# DSPA.net
KiCad netlist of a schematic drawn in Altium Designer
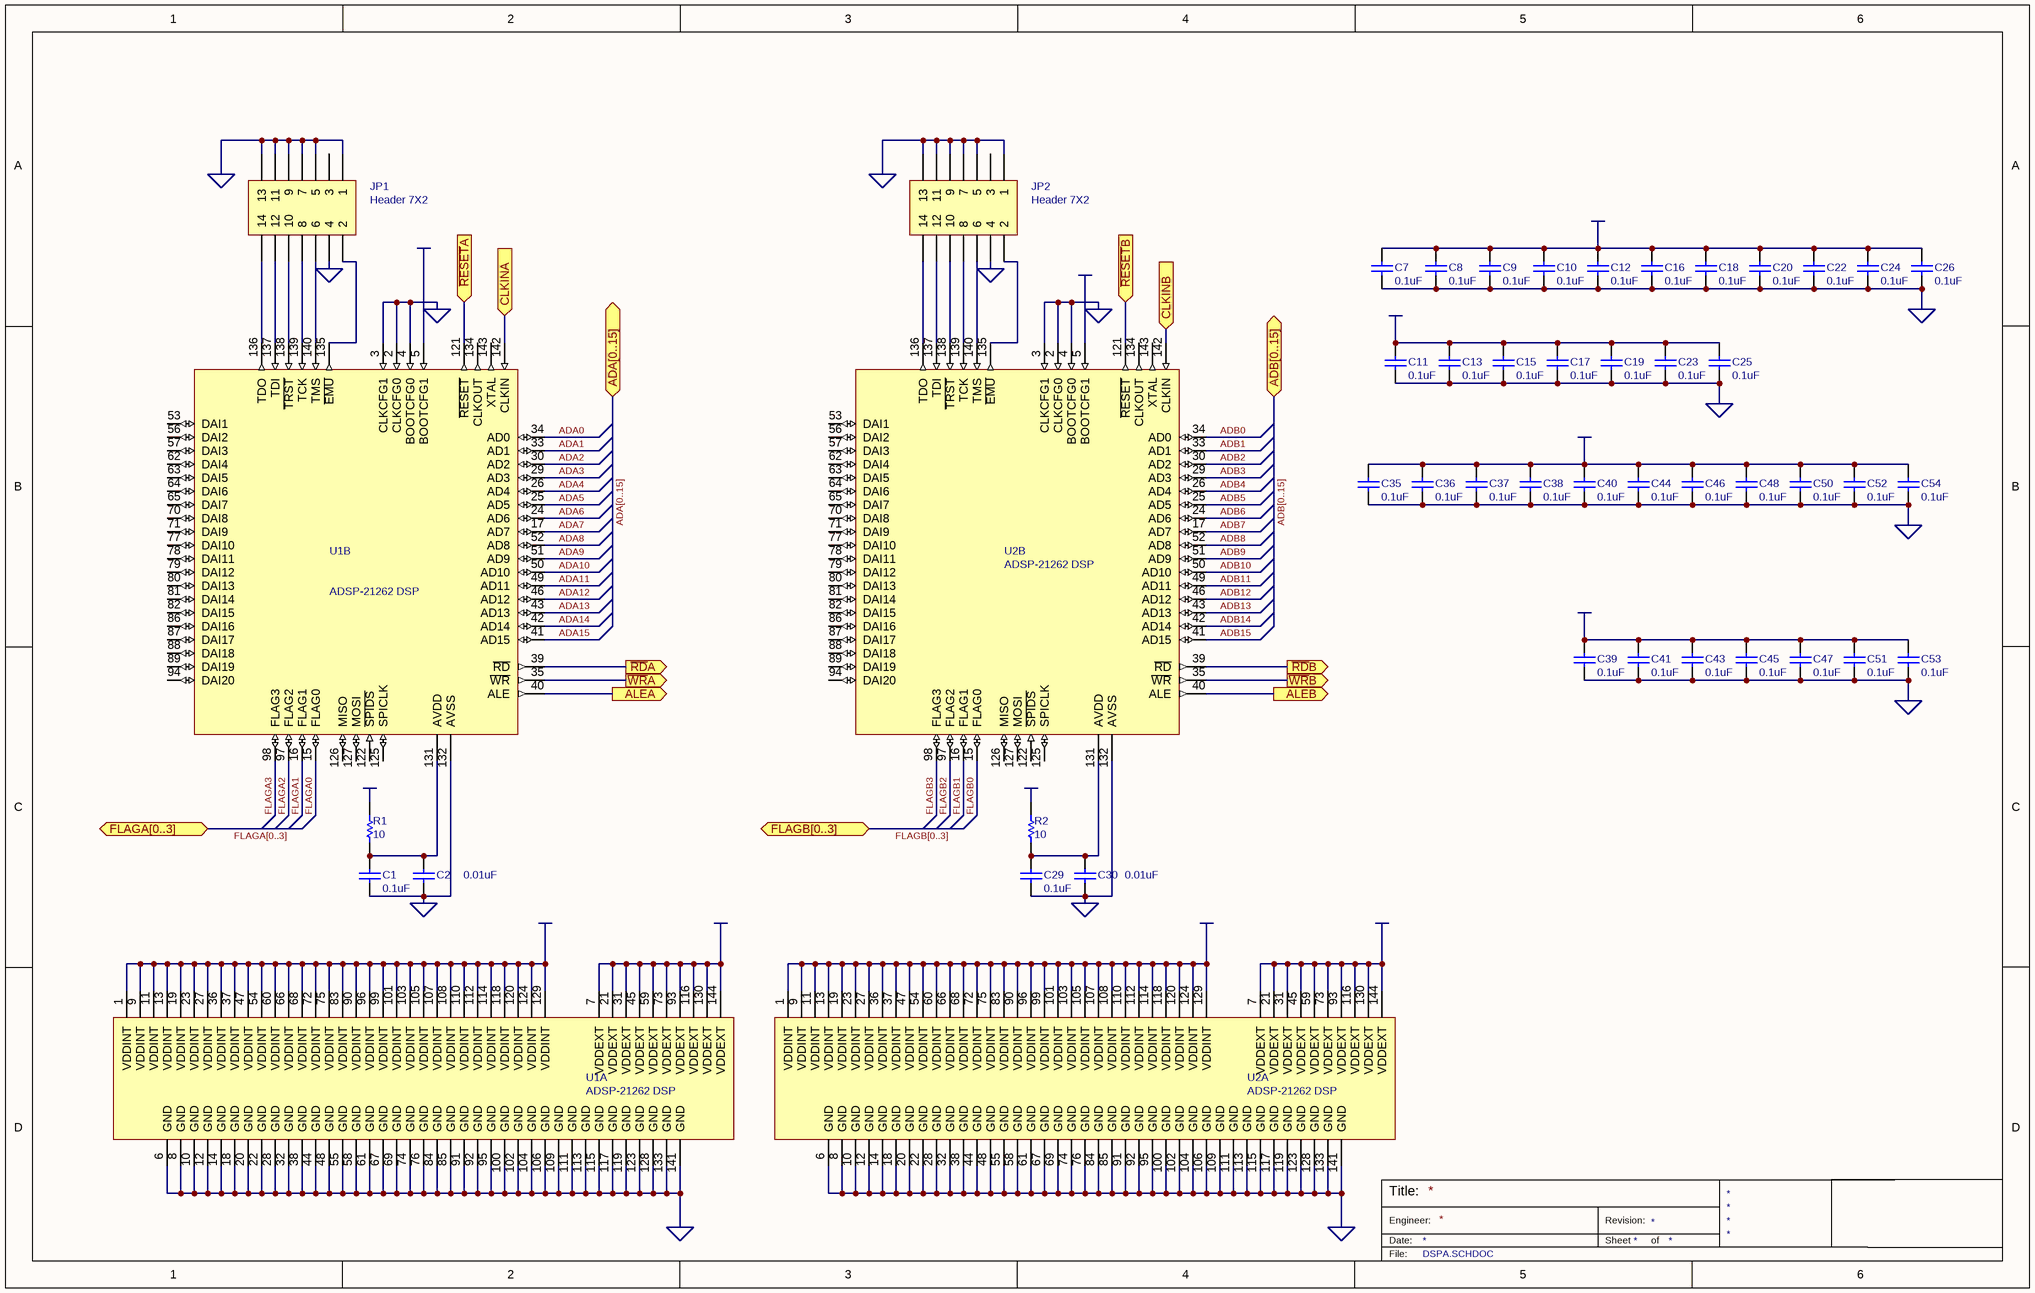
[diagram p0: DSPA.SCHDOC]

(export (version "E")
  (design (tool "Eeschema 10.0.6"))
  (components
    (comp (ref "C1")
      (value "0.1uF")
      (footprint "CC1005-0402")
      (description "Capacitor")
      (fields
        (field (name "MANUFACTURER") "Generic Components")
        (field (name "Comment") "Cap")
        (field (name "PUBLISHER") "Altium Limited")
      )
      (libsource (lib "Miscellaneous Devices") (part "Cap"))
    )
    (comp (ref "C2")
      (value "0.01uF")
      (footprint "CC1005-0402")
      (description "Capacitor")
      (fields
        (field (name "MANUFACTURER") "Generic Components")
        (field (name "Comment") "Cap")
        (field (name "PUBLISHER") "Altium Limited")
      )
      (libsource (lib "Miscellaneous Devices") (part "Cap"))
    )
    (comp (ref "C7")
      (value "0.1uF")
      (footprint "CC1005-0402")
      (description "Capacitor")
      (fields
        (field (name "MANUFACTURER") "Generic Components")
        (field (name "Comment") "Cap")
        (field (name "PUBLISHER") "Altium Limited")
      )
      (libsource (lib "Miscellaneous Devices") (part "Cap"))
    )
    (comp (ref "C8")
      (value "0.1uF")
      (footprint "CC1005-0402")
      (description "Capacitor")
      (fields
        (field (name "MANUFACTURER") "Generic Components")
        (field (name "Comment") "Cap")
        (field (name "PUBLISHER") "Altium Limited")
      )
      (libsource (lib "Miscellaneous Devices") (part "Cap"))
    )
    (comp (ref "C9")
      (value "0.1uF")
      (footprint "CC1005-0402")
      (description "Capacitor")
      (fields
        (field (name "MANUFACTURER") "Generic Components")
        (field (name "Comment") "Cap")
        (field (name "PUBLISHER") "Altium Limited")
      )
      (libsource (lib "Miscellaneous Devices") (part "Cap"))
    )
    (comp (ref "C10")
      (value "0.1uF")
      (footprint "CC1005-0402")
      (description "Capacitor")
      (fields
        (field (name "MANUFACTURER") "Generic Components")
        (field (name "Comment") "Cap")
        (field (name "PUBLISHER") "Altium Limited")
      )
      (libsource (lib "Miscellaneous Devices") (part "Cap"))
    )
    (comp (ref "C11")
      (value "0.1uF")
      (footprint "CC1005-0402")
      (description "Capacitor")
      (fields
        (field (name "MANUFACTURER") "Generic Components")
        (field (name "Comment") "Cap")
        (field (name "PUBLISHER") "Altium Limited")
      )
      (libsource (lib "Miscellaneous Devices") (part "Cap"))
    )
    (comp (ref "C12")
      (value "0.1uF")
      (footprint "CC1005-0402")
      (description "Capacitor")
      (fields
        (field (name "MANUFACTURER") "Generic Components")
        (field (name "Comment") "Cap")
        (field (name "PUBLISHER") "Altium Limited")
      )
      (libsource (lib "Miscellaneous Devices") (part "Cap"))
    )
    (comp (ref "C13")
      (value "0.1uF")
      (footprint "CC1005-0402")
      (description "Capacitor")
      (fields
        (field (name "MANUFACTURER") "Generic Components")
        (field (name "Comment") "Cap")
        (field (name "PUBLISHER") "Altium Limited")
      )
      (libsource (lib "Miscellaneous Devices") (part "Cap"))
    )
    (comp (ref "C15")
      (value "0.1uF")
      (footprint "CC1005-0402")
      (description "Capacitor")
      (fields
        (field (name "MANUFACTURER") "Generic Components")
        (field (name "Comment") "Cap")
        (field (name "PUBLISHER") "Altium Limited")
      )
      (libsource (lib "Miscellaneous Devices") (part "Cap"))
    )
    (comp (ref "C16")
      (value "0.1uF")
      (footprint "CC1005-0402")
      (description "Capacitor")
      (fields
        (field (name "MANUFACTURER") "Generic Components")
        (field (name "Comment") "Cap")
        (field (name "PUBLISHER") "Altium Limited")
      )
      (libsource (lib "Miscellaneous Devices") (part "Cap"))
    )
    (comp (ref "C17")
      (value "0.1uF")
      (footprint "CC1005-0402")
      (description "Capacitor")
      (fields
        (field (name "MANUFACTURER") "Generic Components")
        (field (name "Comment") "Cap")
        (field (name "PUBLISHER") "Altium Limited")
      )
      (libsource (lib "Miscellaneous Devices") (part "Cap"))
    )
    (comp (ref "C18")
      (value "0.1uF")
      (footprint "CC1005-0402")
      (description "Capacitor")
      (fields
        (field (name "MANUFACTURER") "Generic Components")
        (field (name "Comment") "Cap")
        (field (name "PUBLISHER") "Altium Limited")
      )
      (libsource (lib "Miscellaneous Devices") (part "Cap"))
    )
    (comp (ref "C19")
      (value "0.1uF")
      (footprint "CC1005-0402")
      (description "Capacitor")
      (fields
        (field (name "MANUFACTURER") "Generic Components")
        (field (name "Comment") "Cap")
        (field (name "PUBLISHER") "Altium Limited")
      )
      (libsource (lib "Miscellaneous Devices") (part "Cap"))
    )
    (comp (ref "C20")
      (value "0.1uF")
      (footprint "CC1005-0402")
      (description "Capacitor")
      (fields
        (field (name "MANUFACTURER") "Generic Components")
        (field (name "Comment") "Cap")
        (field (name "PUBLISHER") "Altium Limited")
      )
      (libsource (lib "Miscellaneous Devices") (part "Cap"))
    )
    (comp (ref "C22")
      (value "0.1uF")
      (footprint "CC1005-0402")
      (description "Capacitor")
      (fields
        (field (name "MANUFACTURER") "Generic Components")
        (field (name "Comment") "Cap")
        (field (name "PUBLISHER") "Altium Limited")
      )
      (libsource (lib "Miscellaneous Devices") (part "Cap"))
    )
    (comp (ref "C23")
      (value "0.1uF")
      (footprint "CC1005-0402")
      (description "Capacitor")
      (fields
        (field (name "MANUFACTURER") "Generic Components")
        (field (name "Comment") "Cap")
        (field (name "PUBLISHER") "Altium Limited")
      )
      (libsource (lib "Miscellaneous Devices") (part "Cap"))
    )
    (comp (ref "C24")
      (value "0.1uF")
      (footprint "CC1005-0402")
      (description "Capacitor")
      (fields
        (field (name "MANUFACTURER") "Generic Components")
        (field (name "Comment") "Cap")
        (field (name "PUBLISHER") "Altium Limited")
      )
      (libsource (lib "Miscellaneous Devices") (part "Cap"))
    )
    (comp (ref "C25")
      (value "0.1uF")
      (footprint "CC1005-0402")
      (description "Capacitor")
      (fields
        (field (name "MANUFACTURER") "Generic Components")
        (field (name "Comment") "Cap")
        (field (name "PUBLISHER") "Altium Limited")
      )
      (libsource (lib "Miscellaneous Devices") (part "Cap"))
    )
    (comp (ref "C26")
      (value "0.1uF")
      (footprint "CC1005-0402")
      (description "Capacitor")
      (fields
        (field (name "MANUFACTURER") "Generic Components")
        (field (name "Comment") "Cap")
        (field (name "PUBLISHER") "Altium Limited")
      )
      (libsource (lib "Miscellaneous Devices") (part "Cap"))
    )
    (comp (ref "C29")
      (value "0.1uF")
      (footprint "CC1005-0402")
      (description "Capacitor")
      (fields
        (field (name "MANUFACTURER") "Generic Components")
        (field (name "Comment") "Cap")
        (field (name "PUBLISHER") "Altium Limited")
      )
      (libsource (lib "Miscellaneous Devices") (part "Cap"))
    )
    (comp (ref "C30")
      (value "0.01uF")
      (footprint "CC1005-0402")
      (description "Capacitor")
      (fields
        (field (name "MANUFACTURER") "Generic Components")
        (field (name "Comment") "Cap")
        (field (name "PUBLISHER") "Altium Limited")
      )
      (libsource (lib "Miscellaneous Devices") (part "Cap"))
    )
    (comp (ref "C35")
      (value "0.1uF")
      (footprint "CC1005-0402")
      (description "Capacitor")
      (fields
        (field (name "MANUFACTURER") "Generic Components")
        (field (name "Comment") "Cap")
        (field (name "PUBLISHER") "Altium Limited")
      )
      (libsource (lib "Miscellaneous Devices") (part "Cap"))
    )
    (comp (ref "C36")
      (value "0.1uF")
      (footprint "CC1005-0402")
      (description "Capacitor")
      (fields
        (field (name "MANUFACTURER") "Generic Components")
        (field (name "Comment") "Cap")
        (field (name "PUBLISHER") "Altium Limited")
      )
      (libsource (lib "Miscellaneous Devices") (part "Cap"))
    )
    (comp (ref "C37")
      (value "0.1uF")
      (footprint "CC1005-0402")
      (description "Capacitor")
      (fields
        (field (name "MANUFACTURER") "Generic Components")
        (field (name "Comment") "Cap")
        (field (name "PUBLISHER") "Altium Limited")
      )
      (libsource (lib "Miscellaneous Devices") (part "Cap"))
    )
    (comp (ref "C38")
      (value "0.1uF")
      (footprint "CC1005-0402")
      (description "Capacitor")
      (fields
        (field (name "MANUFACTURER") "Generic Components")
        (field (name "Comment") "Cap")
        (field (name "PUBLISHER") "Altium Limited")
      )
      (libsource (lib "Miscellaneous Devices") (part "Cap"))
    )
    (comp (ref "C39")
      (value "0.1uF")
      (footprint "CC1005-0402")
      (description "Capacitor")
      (fields
        (field (name "MANUFACTURER") "Generic Components")
        (field (name "Comment") "Cap")
        (field (name "PUBLISHER") "Altium Limited")
      )
      (libsource (lib "Miscellaneous Devices") (part "Cap"))
    )
    (comp (ref "C40")
      (value "0.1uF")
      (footprint "CC1005-0402")
      (description "Capacitor")
      (fields
        (field (name "MANUFACTURER") "Generic Components")
        (field (name "Comment") "Cap")
        (field (name "PUBLISHER") "Altium Limited")
      )
      (libsource (lib "Miscellaneous Devices") (part "Cap"))
    )
    (comp (ref "C41")
      (value "0.1uF")
      (footprint "CC1005-0402")
      (description "Capacitor")
      (fields
        (field (name "MANUFACTURER") "Generic Components")
        (field (name "Comment") "Cap")
        (field (name "PUBLISHER") "Altium Limited")
      )
      (libsource (lib "Miscellaneous Devices") (part "Cap"))
    )
    (comp (ref "C43")
      (value "0.1uF")
      (footprint "CC1005-0402")
      (description "Capacitor")
      (fields
        (field (name "MANUFACTURER") "Generic Components")
        (field (name "Comment") "Cap")
        (field (name "PUBLISHER") "Altium Limited")
      )
      (libsource (lib "Miscellaneous Devices") (part "Cap"))
    )
    (comp (ref "C44")
      (value "0.1uF")
      (footprint "CC1005-0402")
      (description "Capacitor")
      (fields
        (field (name "MANUFACTURER") "Generic Components")
        (field (name "Comment") "Cap")
        (field (name "PUBLISHER") "Altium Limited")
      )
      (libsource (lib "Miscellaneous Devices") (part "Cap"))
    )
    (comp (ref "C45")
      (value "0.1uF")
      (footprint "CC1005-0402")
      (description "Capacitor")
      (fields
        (field (name "MANUFACTURER") "Generic Components")
        (field (name "Comment") "Cap")
        (field (name "PUBLISHER") "Altium Limited")
      )
      (libsource (lib "Miscellaneous Devices") (part "Cap"))
    )
    (comp (ref "C46")
      (value "0.1uF")
      (footprint "CC1005-0402")
      (description "Capacitor")
      (fields
        (field (name "MANUFACTURER") "Generic Components")
        (field (name "Comment") "Cap")
        (field (name "PUBLISHER") "Altium Limited")
      )
      (libsource (lib "Miscellaneous Devices") (part "Cap"))
    )
    (comp (ref "C47")
      (value "0.1uF")
      (footprint "CC1005-0402")
      (description "Capacitor")
      (fields
        (field (name "MANUFACTURER") "Generic Components")
        (field (name "Comment") "Cap")
        (field (name "PUBLISHER") "Altium Limited")
      )
      (libsource (lib "Miscellaneous Devices") (part "Cap"))
    )
    (comp (ref "C48")
      (value "0.1uF")
      (footprint "CC1005-0402")
      (description "Capacitor")
      (fields
        (field (name "MANUFACTURER") "Generic Components")
        (field (name "Comment") "Cap")
        (field (name "PUBLISHER") "Altium Limited")
      )
      (libsource (lib "Miscellaneous Devices") (part "Cap"))
    )
    (comp (ref "C50")
      (value "0.1uF")
      (footprint "CC1005-0402")
      (description "Capacitor")
      (fields
        (field (name "MANUFACTURER") "Generic Components")
        (field (name "Comment") "Cap")
        (field (name "PUBLISHER") "Altium Limited")
      )
      (libsource (lib "Miscellaneous Devices") (part "Cap"))
    )
    (comp (ref "C51")
      (value "0.1uF")
      (footprint "CC1005-0402")
      (description "Capacitor")
      (fields
        (field (name "MANUFACTURER") "Generic Components")
        (field (name "Comment") "Cap")
        (field (name "PUBLISHER") "Altium Limited")
      )
      (libsource (lib "Miscellaneous Devices") (part "Cap"))
    )
    (comp (ref "C52")
      (value "0.1uF")
      (footprint "CC1005-0402")
      (description "Capacitor")
      (fields
        (field (name "MANUFACTURER") "Generic Components")
        (field (name "Comment") "Cap")
        (field (name "PUBLISHER") "Altium Limited")
      )
      (libsource (lib "Miscellaneous Devices") (part "Cap"))
    )
    (comp (ref "C53")
      (value "0.1uF")
      (footprint "CC1005-0402")
      (description "Capacitor")
      (fields
        (field (name "MANUFACTURER") "Generic Components")
        (field (name "Comment") "Cap")
        (field (name "PUBLISHER") "Altium Limited")
      )
      (libsource (lib "Miscellaneous Devices") (part "Cap"))
    )
    (comp (ref "C54")
      (value "0.1uF")
      (footprint "CC1005-0402")
      (description "Capacitor")
      (fields
        (field (name "MANUFACTURER") "Generic Components")
        (field (name "Comment") "Cap")
        (field (name "PUBLISHER") "Altium Limited")
      )
      (libsource (lib "Miscellaneous Devices") (part "Cap"))
    )
    (comp (ref "JP1")
      (value "Header 7X2")
      (footprint "HDR2X7")
      (description "Header, 7-Pin, Dual row")
      (fields (field (name "MANUFACTURER") "Generic Components") (field (name "PUBLISHER") "Altium Limited"))
      (libsource (lib "Miscellaneous Connectors") (part "Header 7X2"))
    )
    (comp (ref "JP2")
      (value "Header 7X2")
      (footprint "HDR2X7")
      (description "Header, 7-Pin, Dual row")
      (fields (field (name "MANUFACTURER") "Generic Components") (field (name "PUBLISHER") "Altium Limited"))
      (libsource (lib "Miscellaneous Connectors") (part "Header 7X2"))
    )
    (comp (ref "R1")
      (value "10")
      (footprint "CR1608-0603")
      (description "Resistor")
      (fields
        (field (name "MANUFACTURER") "Generic Components")
        (field (name "Comment") "Res1")
        (field (name "PUBLISHER") "Altium Limited")
      )
      (libsource (lib "Miscellaneous Devices") (part "Res1"))
    )
    (comp (ref "R2")
      (value "10")
      (footprint "CR1608-0603")
      (description "Resistor")
      (fields
        (field (name "MANUFACTURER") "Generic Components")
        (field (name "Comment") "Res1")
        (field (name "PUBLISHER") "Altium Limited")
      )
      (libsource (lib "Miscellaneous Devices") (part "Res1"))
    )
    (comp (ref "U1")
      (value "ADSP-21262 DSP")
      (footprint "F-QFP20X20-G144/N")
      (description "SHARC 200 MHz 32-bit floating-point SIMD DSP")
      (libsource (lib "parts") (part "ADSP-21262"))
    )
    (comp (ref "U2")
      (value "ADSP-21262 DSP")
      (footprint "F-QFP20X20-G144/N")
      (description "SHARC 200 MHz 32-bit floating-point SIMD DSP")
      (libsource (lib "parts") (part "ADSP-21262"))
    )
  )
  (nets
    (net (code "1") (name "+1.2VCC") (class "Default")
      (node (ref "C10") (pin "2") (pinfunction "2_2") (pintype "passive"))
      (node (ref "C12") (pin "2") (pinfunction "2_2") (pintype "passive"))
      (node (ref "C16") (pin "2") (pinfunction "2_2") (pintype "passive"))
      (node (ref "C18") (pin "2") (pinfunction "2_2") (pintype "passive"))
      (node (ref "C20") (pin "2") (pinfunction "2_2") (pintype "passive"))
      (node (ref "C22") (pin "2") (pinfunction "2_2") (pintype "passive"))
      (node (ref "C24") (pin "2") (pinfunction "2_2") (pintype "passive"))
      (node (ref "C26") (pin "2") (pinfunction "2_2") (pintype "passive"))
      (node (ref "C35") (pin "2") (pinfunction "2_2") (pintype "passive"))
      (node (ref "C36") (pin "2") (pinfunction "2_2") (pintype "passive"))
      (node (ref "C37") (pin "2") (pinfunction "2_2") (pintype "passive"))
      (node (ref "C38") (pin "2") (pinfunction "2_2") (pintype "passive"))
      (node (ref "C40") (pin "2") (pinfunction "2_2") (pintype "passive"))
      (node (ref "C44") (pin "2") (pinfunction "2_2") (pintype "passive"))
      (node (ref "C46") (pin "2") (pinfunction "2_2") (pintype "passive"))
      (node (ref "C48") (pin "2") (pinfunction "2_2") (pintype "passive"))
      (node (ref "C50") (pin "2") (pinfunction "2_2") (pintype "passive"))
      (node (ref "C52") (pin "2") (pinfunction "2_2") (pintype "passive"))
      (node (ref "C54") (pin "2") (pinfunction "2_2") (pintype "passive"))
      (node (ref "C7") (pin "2") (pinfunction "2_2") (pintype "passive"))
      (node (ref "C8") (pin "2") (pinfunction "2_2") (pintype "passive"))
      (node (ref "C9") (pin "2") (pinfunction "2_2") (pintype "passive"))
      (node (ref "R1") (pin "1") (pinfunction "1_1") (pintype "passive"))
      (node (ref "R2") (pin "1") (pinfunction "1_1") (pintype "passive"))
      (node (ref "U1") (pin "1") (pinfunction "VDDINT_1") (pintype "power_in"))
      (node (ref "U1") (pin "101") (pinfunction "VDDINT_101") (pintype "power_in"))
      (node (ref "U1") (pin "103") (pinfunction "VDDINT_103") (pintype "power_in"))
      (node (ref "U1") (pin "105") (pinfunction "VDDINT_105") (pintype "power_in"))
      (node (ref "U1") (pin "107") (pinfunction "VDDINT_107") (pintype "power_in"))
      (node (ref "U1") (pin "108") (pinfunction "VDDINT_108") (pintype "power_in"))
      (node (ref "U1") (pin "11") (pinfunction "VDDINT_11") (pintype "power_in"))
      (node (ref "U1") (pin "110") (pinfunction "VDDINT_110") (pintype "power_in"))
      (node (ref "U1") (pin "112") (pinfunction "VDDINT_112") (pintype "power_in"))
      (node (ref "U1") (pin "114") (pinfunction "VDDINT_114") (pintype "power_in"))
      (node (ref "U1") (pin "118") (pinfunction "VDDINT_118") (pintype "power_in"))
      (node (ref "U1") (pin "120") (pinfunction "VDDINT_120") (pintype "power_in"))
      (node (ref "U1") (pin "124") (pinfunction "VDDINT_124") (pintype "power_in"))
      (node (ref "U1") (pin "129") (pinfunction "VDDINT_129") (pintype "power_in"))
      (node (ref "U1") (pin "13") (pinfunction "VDDINT_13") (pintype "power_in"))
      (node (ref "U1") (pin "19") (pinfunction "VDDINT_19") (pintype "power_in"))
      (node (ref "U1") (pin "23") (pinfunction "VDDINT_23") (pintype "power_in"))
      (node (ref "U1") (pin "27") (pinfunction "VDDINT_27") (pintype "power_in"))
      (node (ref "U1") (pin "36") (pinfunction "VDDINT_36") (pintype "power_in"))
      (node (ref "U1") (pin "37") (pinfunction "VDDINT_37") (pintype "power_in"))
      (node (ref "U1") (pin "47") (pinfunction "VDDINT_47") (pintype "power_in"))
      (node (ref "U1") (pin "54") (pinfunction "VDDINT_54") (pintype "power_in"))
      (node (ref "U1") (pin "60") (pinfunction "VDDINT_60") (pintype "power_in"))
      (node (ref "U1") (pin "66") (pinfunction "VDDINT_66") (pintype "power_in"))
      (node (ref "U1") (pin "68") (pinfunction "VDDINT_68") (pintype "power_in"))
      (node (ref "U1") (pin "72") (pinfunction "VDDINT_72") (pintype "power_in"))
      (node (ref "U1") (pin "75") (pinfunction "VDDINT_75") (pintype "power_in"))
      (node (ref "U1") (pin "83") (pinfunction "VDDINT_83") (pintype "power_in"))
      (node (ref "U1") (pin "9") (pinfunction "VDDINT_9") (pintype "power_in"))
      (node (ref "U1") (pin "90") (pinfunction "VDDINT_90") (pintype "power_in"))
      (node (ref "U1") (pin "96") (pinfunction "VDDINT_96") (pintype "power_in"))
      (node (ref "U1") (pin "99") (pinfunction "VDDINT_99") (pintype "power_in"))
      (node (ref "U2") (pin "1") (pinfunction "VDDINT_1") (pintype "power_in"))
      (node (ref "U2") (pin "101") (pinfunction "VDDINT_101") (pintype "power_in"))
      (node (ref "U2") (pin "103") (pinfunction "VDDINT_103") (pintype "power_in"))
      (node (ref "U2") (pin "105") (pinfunction "VDDINT_105") (pintype "power_in"))
      (node (ref "U2") (pin "107") (pinfunction "VDDINT_107") (pintype "power_in"))
      (node (ref "U2") (pin "108") (pinfunction "VDDINT_108") (pintype "power_in"))
      (node (ref "U2") (pin "11") (pinfunction "VDDINT_11") (pintype "power_in"))
      (node (ref "U2") (pin "110") (pinfunction "VDDINT_110") (pintype "power_in"))
      (node (ref "U2") (pin "112") (pinfunction "VDDINT_112") (pintype "power_in"))
      (node (ref "U2") (pin "114") (pinfunction "VDDINT_114") (pintype "power_in"))
      (node (ref "U2") (pin "118") (pinfunction "VDDINT_118") (pintype "power_in"))
      (node (ref "U2") (pin "120") (pinfunction "VDDINT_120") (pintype "power_in"))
      (node (ref "U2") (pin "124") (pinfunction "VDDINT_124") (pintype "power_in"))
      (node (ref "U2") (pin "129") (pinfunction "VDDINT_129") (pintype "power_in"))
      (node (ref "U2") (pin "13") (pinfunction "VDDINT_13") (pintype "power_in"))
      (node (ref "U2") (pin "19") (pinfunction "VDDINT_19") (pintype "power_in"))
      (node (ref "U2") (pin "23") (pinfunction "VDDINT_23") (pintype "power_in"))
      (node (ref "U2") (pin "27") (pinfunction "VDDINT_27") (pintype "power_in"))
      (node (ref "U2") (pin "36") (pinfunction "VDDINT_36") (pintype "power_in"))
      (node (ref "U2") (pin "37") (pinfunction "VDDINT_37") (pintype "power_in"))
      (node (ref "U2") (pin "47") (pinfunction "VDDINT_47") (pintype "power_in"))
      (node (ref "U2") (pin "54") (pinfunction "VDDINT_54") (pintype "power_in"))
      (node (ref "U2") (pin "60") (pinfunction "VDDINT_60") (pintype "power_in"))
      (node (ref "U2") (pin "66") (pinfunction "VDDINT_66") (pintype "power_in"))
      (node (ref "U2") (pin "68") (pinfunction "VDDINT_68") (pintype "power_in"))
      (node (ref "U2") (pin "72") (pinfunction "VDDINT_72") (pintype "power_in"))
      (node (ref "U2") (pin "75") (pinfunction "VDDINT_75") (pintype "power_in"))
      (node (ref "U2") (pin "83") (pinfunction "VDDINT_83") (pintype "power_in"))
      (node (ref "U2") (pin "9") (pinfunction "VDDINT_9") (pintype "power_in"))
      (node (ref "U2") (pin "90") (pinfunction "VDDINT_90") (pintype "power_in"))
      (node (ref "U2") (pin "96") (pinfunction "VDDINT_96") (pintype "power_in"))
      (node (ref "U2") (pin "99") (pinfunction "VDDINT_99") (pintype "power_in"))
    )
    (net (code "2") (name "/ADA0") (class "Default")
      (node (ref "U1") (pin "34") (pinfunction "AD0_34") (pintype "bidirectional"))
    )
    (net (code "3") (name "/ADA1") (class "Default")
      (node (ref "U1") (pin "33") (pinfunction "AD1_33") (pintype "bidirectional"))
    )
    (net (code "4") (name "/ADA2") (class "Default")
      (node (ref "U1") (pin "30") (pinfunction "AD2_30") (pintype "bidirectional"))
    )
    (net (code "5") (name "/ADA3") (class "Default")
      (node (ref "U1") (pin "29") (pinfunction "AD3_29") (pintype "bidirectional"))
    )
    (net (code "6") (name "/ADA4") (class "Default")
      (node (ref "U1") (pin "26") (pinfunction "AD4_26") (pintype "bidirectional"))
    )
    (net (code "7") (name "/ADA5") (class "Default")
      (node (ref "U1") (pin "25") (pinfunction "AD5_25") (pintype "bidirectional"))
    )
    (net (code "8") (name "/ADA6") (class "Default")
      (node (ref "U1") (pin "24") (pinfunction "AD6_24") (pintype "bidirectional"))
    )
    (net (code "9") (name "/ADA7") (class "Default")
      (node (ref "U1") (pin "17") (pinfunction "AD7_17") (pintype "bidirectional"))
    )
    (net (code "10") (name "/ADA8") (class "Default")
      (node (ref "U1") (pin "52") (pinfunction "AD8_52") (pintype "bidirectional"))
    )
    (net (code "11") (name "/ADA9") (class "Default")
      (node (ref "U1") (pin "51") (pinfunction "AD9_51") (pintype "bidirectional"))
    )
    (net (code "12") (name "/ADA10") (class "Default")
      (node (ref "U1") (pin "50") (pinfunction "AD10_50") (pintype "bidirectional"))
    )
    (net (code "13") (name "/ADA11") (class "Default")
      (node (ref "U1") (pin "49") (pinfunction "AD11_49") (pintype "bidirectional"))
    )
    (net (code "14") (name "/ADA12") (class "Default")
      (node (ref "U1") (pin "46") (pinfunction "AD12_46") (pintype "bidirectional"))
    )
    (net (code "15") (name "/ADA13") (class "Default")
      (node (ref "U1") (pin "43") (pinfunction "AD13_43") (pintype "bidirectional"))
    )
    (net (code "16") (name "/ADA14") (class "Default")
      (node (ref "U1") (pin "42") (pinfunction "AD14_42") (pintype "bidirectional"))
    )
    (net (code "17") (name "/ADA15") (class "Default")
      (node (ref "U1") (pin "41") (pinfunction "AD15_41") (pintype "bidirectional"))
    )
    (net (code "19") (name "/ADB0") (class "Default")
      (node (ref "U2") (pin "34") (pinfunction "AD0_34") (pintype "bidirectional"))
    )
    (net (code "20") (name "/ADB1") (class "Default")
      (node (ref "U2") (pin "33") (pinfunction "AD1_33") (pintype "bidirectional"))
    )
    (net (code "21") (name "/ADB2") (class "Default")
      (node (ref "U2") (pin "30") (pinfunction "AD2_30") (pintype "bidirectional"))
    )
    (net (code "22") (name "/ADB3") (class "Default")
      (node (ref "U2") (pin "29") (pinfunction "AD3_29") (pintype "bidirectional"))
    )
    (net (code "23") (name "/ADB4") (class "Default")
      (node (ref "U2") (pin "26") (pinfunction "AD4_26") (pintype "bidirectional"))
    )
    (net (code "24") (name "/ADB5") (class "Default")
      (node (ref "U2") (pin "25") (pinfunction "AD5_25") (pintype "bidirectional"))
    )
    (net (code "25") (name "/ADB6") (class "Default")
      (node (ref "U2") (pin "24") (pinfunction "AD6_24") (pintype "bidirectional"))
    )
    (net (code "26") (name "/ADB7") (class "Default")
      (node (ref "U2") (pin "17") (pinfunction "AD7_17") (pintype "bidirectional"))
    )
    (net (code "27") (name "/ADB8") (class "Default")
      (node (ref "U2") (pin "52") (pinfunction "AD8_52") (pintype "bidirectional"))
    )
    (net (code "28") (name "/ADB9") (class "Default")
      (node (ref "U2") (pin "51") (pinfunction "AD9_51") (pintype "bidirectional"))
    )
    (net (code "29") (name "/ADB10") (class "Default")
      (node (ref "U2") (pin "50") (pinfunction "AD10_50") (pintype "bidirectional"))
    )
    (net (code "30") (name "/ADB11") (class "Default")
      (node (ref "U2") (pin "49") (pinfunction "AD11_49") (pintype "bidirectional"))
    )
    (net (code "31") (name "/ADB12") (class "Default")
      (node (ref "U2") (pin "46") (pinfunction "AD12_46") (pintype "bidirectional"))
    )
    (net (code "32") (name "/ADB13") (class "Default")
      (node (ref "U2") (pin "43") (pinfunction "AD13_43") (pintype "bidirectional"))
    )
    (net (code "33") (name "/ADB14") (class "Default")
      (node (ref "U2") (pin "42") (pinfunction "AD14_42") (pintype "bidirectional"))
    )
    (net (code "34") (name "/ADB15") (class "Default")
      (node (ref "U2") (pin "41") (pinfunction "AD15_41") (pintype "bidirectional"))
    )
    (net (code "36") (name "/ALEA") (class "Default")
      (node (ref "U1") (pin "40") (pinfunction "ALE_40") (pintype "output"))
    )
    (net (code "37") (name "/ALEB") (class "Default")
      (node (ref "U2") (pin "40") (pinfunction "ALE_40") (pintype "output"))
    )
    (net (code "38") (name "/CLKINA") (class "Default")
      (node (ref "U1") (pin "142") (pinfunction "CLKIN_142") (pintype "input"))
    )
    (net (code "39") (name "/CLKINB") (class "Default")
      (node (ref "U2") (pin "142") (pinfunction "CLKIN_142") (pintype "input"))
    )
    (net (code "40") (name "/FLAGA0") (class "Default")
      (node (ref "U1") (pin "15") (pinfunction "FLAG0_15") (pintype "bidirectional"))
    )
    (net (code "41") (name "/FLAGA1") (class "Default")
      (node (ref "U1") (pin "16") (pinfunction "FLAG1_16") (pintype "bidirectional"))
    )
    (net (code "42") (name "/FLAGA2") (class "Default")
      (node (ref "U1") (pin "97") (pinfunction "FLAG2_97") (pintype "bidirectional"))
    )
    (net (code "43") (name "/FLAGA3") (class "Default")
      (node (ref "U1") (pin "98") (pinfunction "FLAG3_98") (pintype "bidirectional"))
    )
    (net (code "45") (name "/FLAGB0") (class "Default")
      (node (ref "U2") (pin "15") (pinfunction "FLAG0_15") (pintype "bidirectional"))
    )
    (net (code "46") (name "/FLAGB1") (class "Default")
      (node (ref "U2") (pin "16") (pinfunction "FLAG1_16") (pintype "bidirectional"))
    )
    (net (code "47") (name "/FLAGB2") (class "Default")
      (node (ref "U2") (pin "97") (pinfunction "FLAG2_97") (pintype "bidirectional"))
    )
    (net (code "48") (name "/FLAGB3") (class "Default")
      (node (ref "U2") (pin "98") (pinfunction "FLAG3_98") (pintype "bidirectional"))
    )
    (net (code "50") (name "/~{RD}A") (class "Default")
      (node (ref "U1") (pin "39") (pinfunction "~{RD}_39") (pintype "output"))
    )
    (net (code "51") (name "/~{RD}B") (class "Default")
      (node (ref "U2") (pin "39") (pinfunction "~{RD}_39") (pintype "output"))
    )
    (net (code "52") (name "/~{RESET}A") (class "Default")
      (node (ref "U1") (pin "121") (pinfunction "~{RESET}_121") (pintype "output"))
    )
    (net (code "53") (name "/~{RESET}B") (class "Default")
      (node (ref "U2") (pin "121") (pinfunction "~{RESET}_121") (pintype "output"))
    )
    (net (code "54") (name "/~{WR}A") (class "Default")
      (node (ref "U1") (pin "35") (pinfunction "~{WR}_35") (pintype "output"))
    )
    (net (code "55") (name "/~{WR}B") (class "Default")
      (node (ref "U2") (pin "35") (pinfunction "~{WR}_35") (pintype "output"))
    )
    (net (code "56") (name "GND") (class "Default")
      (node (ref "C1") (pin "1") (pinfunction "1_1") (pintype "passive"))
      (node (ref "C10") (pin "1") (pinfunction "1_1") (pintype "passive"))
      (node (ref "C11") (pin "1") (pinfunction "1_1") (pintype "passive"))
      (node (ref "C12") (pin "1") (pinfunction "1_1") (pintype "passive"))
      (node (ref "C13") (pin "1") (pinfunction "1_1") (pintype "passive"))
      (node (ref "C15") (pin "1") (pinfunction "1_1") (pintype "passive"))
      (node (ref "C16") (pin "1") (pinfunction "1_1") (pintype "passive"))
      (node (ref "C17") (pin "1") (pinfunction "1_1") (pintype "passive"))
      (node (ref "C18") (pin "1") (pinfunction "1_1") (pintype "passive"))
      (node (ref "C19") (pin "1") (pinfunction "1_1") (pintype "passive"))
      (node (ref "C2") (pin "1") (pinfunction "1_1") (pintype "passive"))
      (node (ref "C20") (pin "1") (pinfunction "1_1") (pintype "passive"))
      (node (ref "C22") (pin "1") (pinfunction "1_1") (pintype "passive"))
      (node (ref "C23") (pin "1") (pinfunction "1_1") (pintype "passive"))
      (node (ref "C24") (pin "1") (pinfunction "1_1") (pintype "passive"))
      (node (ref "C25") (pin "1") (pinfunction "1_1") (pintype "passive"))
      (node (ref "C26") (pin "1") (pinfunction "1_1") (pintype "passive"))
      (node (ref "C29") (pin "1") (pinfunction "1_1") (pintype "passive"))
      (node (ref "C30") (pin "1") (pinfunction "1_1") (pintype "passive"))
      (node (ref "C35") (pin "1") (pinfunction "1_1") (pintype "passive"))
      (node (ref "C36") (pin "1") (pinfunction "1_1") (pintype "passive"))
      (node (ref "C37") (pin "1") (pinfunction "1_1") (pintype "passive"))
      (node (ref "C38") (pin "1") (pinfunction "1_1") (pintype "passive"))
      (node (ref "C39") (pin "1") (pinfunction "1_1") (pintype "passive"))
      (node (ref "C40") (pin "1") (pinfunction "1_1") (pintype "passive"))
      (node (ref "C41") (pin "1") (pinfunction "1_1") (pintype "passive"))
      (node (ref "C43") (pin "1") (pinfunction "1_1") (pintype "passive"))
      (node (ref "C44") (pin "1") (pinfunction "1_1") (pintype "passive"))
      (node (ref "C45") (pin "1") (pinfunction "1_1") (pintype "passive"))
      (node (ref "C46") (pin "1") (pinfunction "1_1") (pintype "passive"))
      (node (ref "C47") (pin "1") (pinfunction "1_1") (pintype "passive"))
      (node (ref "C48") (pin "1") (pinfunction "1_1") (pintype "passive"))
      (node (ref "C50") (pin "1") (pinfunction "1_1") (pintype "passive"))
      (node (ref "C51") (pin "1") (pinfunction "1_1") (pintype "passive"))
      (node (ref "C52") (pin "1") (pinfunction "1_1") (pintype "passive"))
      (node (ref "C53") (pin "1") (pinfunction "1_1") (pintype "passive"))
      (node (ref "C54") (pin "1") (pinfunction "1_1") (pintype "passive"))
      (node (ref "C7") (pin "1") (pinfunction "1_1") (pintype "passive"))
      (node (ref "C8") (pin "1") (pinfunction "1_1") (pintype "passive"))
      (node (ref "C9") (pin "1") (pinfunction "1_1") (pintype "passive"))
      (node (ref "JP1") (pin "1") (pinfunction "1_1") (pintype "passive"))
      (node (ref "JP1") (pin "11") (pinfunction "11_11") (pintype "passive"))
      (node (ref "JP1") (pin "13") (pinfunction "13_13") (pintype "passive"))
      (node (ref "JP1") (pin "4") (pinfunction "4_4") (pintype "passive"))
      (node (ref "JP1") (pin "5") (pinfunction "5_5") (pintype "passive"))
      (node (ref "JP1") (pin "7") (pinfunction "7_7") (pintype "passive"))
      (node (ref "JP1") (pin "9") (pinfunction "9_9") (pintype "passive"))
      (node (ref "JP2") (pin "1") (pinfunction "1_1") (pintype "passive"))
      (node (ref "JP2") (pin "11") (pinfunction "11_11") (pintype "passive"))
      (node (ref "JP2") (pin "13") (pinfunction "13_13") (pintype "passive"))
      (node (ref "JP2") (pin "4") (pinfunction "4_4") (pintype "passive"))
      (node (ref "JP2") (pin "5") (pinfunction "5_5") (pintype "passive"))
      (node (ref "JP2") (pin "7") (pinfunction "7_7") (pintype "passive"))
      (node (ref "JP2") (pin "9") (pinfunction "9_9") (pintype "passive"))
      (node (ref "U1") (pin "10") (pinfunction "GND_10") (pintype "power_in"))
      (node (ref "U1") (pin "100") (pinfunction "GND_100") (pintype "power_in"))
      (node (ref "U1") (pin "102") (pinfunction "GND_102") (pintype "power_in"))
      (node (ref "U1") (pin "104") (pinfunction "GND_104") (pintype "power_in"))
      (node (ref "U1") (pin "106") (pinfunction "GND_106") (pintype "power_in"))
      (node (ref "U1") (pin "109") (pinfunction "GND_109") (pintype "power_in"))
      (node (ref "U1") (pin "111") (pinfunction "GND_111") (pintype "power_in"))
      (node (ref "U1") (pin "113") (pinfunction "GND_113") (pintype "power_in"))
      (node (ref "U1") (pin "115") (pinfunction "GND_115") (pintype "power_in"))
      (node (ref "U1") (pin "117") (pinfunction "GND_117") (pintype "power_in"))
      (node (ref "U1") (pin "119") (pinfunction "GND_119") (pintype "power_in"))
      (node (ref "U1") (pin "12") (pinfunction "GND_12") (pintype "power_in"))
      (node (ref "U1") (pin "123") (pinfunction "GND_123") (pintype "power_in"))
      (node (ref "U1") (pin "128") (pinfunction "GND_128") (pintype "power_in"))
      (node (ref "U1") (pin "132") (pinfunction "AVSS_132") (pintype "power_in"))
      (node (ref "U1") (pin "133") (pinfunction "GND_133") (pintype "power_in"))
      (node (ref "U1") (pin "14") (pinfunction "GND_14") (pintype "power_in"))
      (node (ref "U1") (pin "141") (pinfunction "GND_141") (pintype "power_in"))
      (node (ref "U1") (pin "18") (pinfunction "GND_18") (pintype "power_in"))
      (node (ref "U1") (pin "2") (pinfunction "CLKCFG0_2") (pintype "input"))
      (node (ref "U1") (pin "20") (pinfunction "GND_20") (pintype "power_in"))
      (node (ref "U1") (pin "22") (pinfunction "GND_22") (pintype "power_in"))
      (node (ref "U1") (pin "28") (pinfunction "GND_28") (pintype "power_in"))
      (node (ref "U1") (pin "3") (pinfunction "CLKCFG1_3") (pintype "input"))
      (node (ref "U1") (pin "32") (pinfunction "GND_32") (pintype "power_in"))
      (node (ref "U1") (pin "38") (pinfunction "GND_38") (pintype "power_in"))
      (node (ref "U1") (pin "4") (pinfunction "BOOTCFG0_4") (pintype "input"))
      (node (ref "U1") (pin "44") (pinfunction "GND_44") (pintype "power_in"))
      (node (ref "U1") (pin "48") (pinfunction "GND_48") (pintype "power_in"))
      (node (ref "U1") (pin "55") (pinfunction "GND_55") (pintype "power_in"))
      (node (ref "U1") (pin "58") (pinfunction "GND_58") (pintype "power_in"))
      (node (ref "U1") (pin "6") (pinfunction "GND_6") (pintype "power_in"))
      (node (ref "U1") (pin "61") (pinfunction "GND_61") (pintype "power_in"))
      (node (ref "U1") (pin "67") (pinfunction "GND_67") (pintype "power_in"))
      (node (ref "U1") (pin "69") (pinfunction "GND_69") (pintype "power_in"))
      (node (ref "U1") (pin "74") (pinfunction "GND_74") (pintype "power_in"))
      (node (ref "U1") (pin "76") (pinfunction "GND_76") (pintype "power_in"))
      (node (ref "U1") (pin "8") (pinfunction "GND_8") (pintype "power_in"))
      (node (ref "U1") (pin "84") (pinfunction "GND_84") (pintype "power_in"))
      (node (ref "U1") (pin "85") (pinfunction "GND_85") (pintype "power_in"))
      (node (ref "U1") (pin "91") (pinfunction "GND_91") (pintype "power_in"))
      (node (ref "U1") (pin "92") (pinfunction "GND_92") (pintype "power_in"))
      (node (ref "U1") (pin "95") (pinfunction "GND_95") (pintype "power_in"))
      (node (ref "U2") (pin "10") (pinfunction "GND_10") (pintype "power_in"))
      (node (ref "U2") (pin "100") (pinfunction "GND_100") (pintype "power_in"))
      (node (ref "U2") (pin "102") (pinfunction "GND_102") (pintype "power_in"))
      (node (ref "U2") (pin "104") (pinfunction "GND_104") (pintype "power_in"))
      (node (ref "U2") (pin "106") (pinfunction "GND_106") (pintype "power_in"))
      (node (ref "U2") (pin "109") (pinfunction "GND_109") (pintype "power_in"))
      (node (ref "U2") (pin "111") (pinfunction "GND_111") (pintype "power_in"))
      (node (ref "U2") (pin "113") (pinfunction "GND_113") (pintype "power_in"))
      (node (ref "U2") (pin "115") (pinfunction "GND_115") (pintype "power_in"))
      (node (ref "U2") (pin "117") (pinfunction "GND_117") (pintype "power_in"))
      (node (ref "U2") (pin "119") (pinfunction "GND_119") (pintype "power_in"))
      (node (ref "U2") (pin "12") (pinfunction "GND_12") (pintype "power_in"))
      (node (ref "U2") (pin "123") (pinfunction "GND_123") (pintype "power_in"))
      (node (ref "U2") (pin "128") (pinfunction "GND_128") (pintype "power_in"))
      (node (ref "U2") (pin "132") (pinfunction "AVSS_132") (pintype "power_in"))
      (node (ref "U2") (pin "133") (pinfunction "GND_133") (pintype "power_in"))
      (node (ref "U2") (pin "14") (pinfunction "GND_14") (pintype "power_in"))
      (node (ref "U2") (pin "141") (pinfunction "GND_141") (pintype "power_in"))
      (node (ref "U2") (pin "18") (pinfunction "GND_18") (pintype "power_in"))
      (node (ref "U2") (pin "2") (pinfunction "CLKCFG0_2") (pintype "input"))
      (node (ref "U2") (pin "20") (pinfunction "GND_20") (pintype "power_in"))
      (node (ref "U2") (pin "22") (pinfunction "GND_22") (pintype "power_in"))
      (node (ref "U2") (pin "28") (pinfunction "GND_28") (pintype "power_in"))
      (node (ref "U2") (pin "3") (pinfunction "CLKCFG1_3") (pintype "input"))
      (node (ref "U2") (pin "32") (pinfunction "GND_32") (pintype "power_in"))
      (node (ref "U2") (pin "38") (pinfunction "GND_38") (pintype "power_in"))
      (node (ref "U2") (pin "4") (pinfunction "BOOTCFG0_4") (pintype "input"))
      (node (ref "U2") (pin "44") (pinfunction "GND_44") (pintype "power_in"))
      (node (ref "U2") (pin "48") (pinfunction "GND_48") (pintype "power_in"))
      (node (ref "U2") (pin "55") (pinfunction "GND_55") (pintype "power_in"))
      (node (ref "U2") (pin "58") (pinfunction "GND_58") (pintype "power_in"))
      (node (ref "U2") (pin "6") (pinfunction "GND_6") (pintype "power_in"))
      (node (ref "U2") (pin "61") (pinfunction "GND_61") (pintype "power_in"))
      (node (ref "U2") (pin "67") (pinfunction "GND_67") (pintype "power_in"))
      (node (ref "U2") (pin "69") (pinfunction "GND_69") (pintype "power_in"))
      (node (ref "U2") (pin "74") (pinfunction "GND_74") (pintype "power_in"))
      (node (ref "U2") (pin "76") (pinfunction "GND_76") (pintype "power_in"))
      (node (ref "U2") (pin "8") (pinfunction "GND_8") (pintype "power_in"))
      (node (ref "U2") (pin "84") (pinfunction "GND_84") (pintype "power_in"))
      (node (ref "U2") (pin "85") (pinfunction "GND_85") (pintype "power_in"))
      (node (ref "U2") (pin "91") (pinfunction "GND_91") (pintype "power_in"))
      (node (ref "U2") (pin "92") (pinfunction "GND_92") (pintype "power_in"))
      (node (ref "U2") (pin "95") (pinfunction "GND_95") (pintype "power_in"))
    )
    (net (code "57") (name "Net-(U1B-AVDD)") (class "Default")
      (node (ref "C1") (pin "2") (pinfunction "2_2") (pintype "passive"))
      (node (ref "C2") (pin "2") (pinfunction "2_2") (pintype "passive"))
      (node (ref "R1") (pin "2") (pinfunction "2_2") (pintype "passive"))
      (node (ref "U1") (pin "131") (pinfunction "AVDD_131") (pintype "power_in"))
    )
    (net (code "58") (name "Net-(U1B-TCK)") (class "Default")
      (node (ref "JP1") (pin "8") (pinfunction "8_8") (pintype "passive"))
      (node (ref "U1") (pin "139") (pinfunction "TCK_139") (pintype "input"))
    )
    (net (code "59") (name "Net-(U1B-TDI)") (class "Default")
      (node (ref "JP1") (pin "12") (pinfunction "12_12") (pintype "passive"))
      (node (ref "U1") (pin "137") (pinfunction "TDI_137") (pintype "input"))
    )
    (net (code "60") (name "Net-(U1B-TDO)") (class "Default")
      (node (ref "JP1") (pin "14") (pinfunction "14_14") (pintype "passive"))
      (node (ref "U1") (pin "136") (pinfunction "TDO_136") (pintype "output"))
    )
    (net (code "61") (name "Net-(U1B-TMS)") (class "Default")
      (node (ref "JP1") (pin "6") (pinfunction "6_6") (pintype "passive"))
      (node (ref "U1") (pin "140") (pinfunction "TMS_140") (pintype "input"))
    )
    (net (code "62") (name "Net-(U1B-~{EMU})") (class "Default")
      (node (ref "JP1") (pin "2") (pinfunction "2_2") (pintype "passive"))
      (node (ref "U1") (pin "135") (pinfunction "~{EMU}_135") (pintype "output"))
    )
    (net (code "63") (name "Net-(U1B-~{TRST})") (class "Default")
      (node (ref "JP1") (pin "10") (pinfunction "10_10") (pintype "passive"))
      (node (ref "U1") (pin "138") (pinfunction "~{TRST}_138") (pintype "input"))
    )
    (net (code "64") (name "Net-(U2B-AVDD)") (class "Default")
      (node (ref "C29") (pin "2") (pinfunction "2_2") (pintype "passive"))
      (node (ref "C30") (pin "2") (pinfunction "2_2") (pintype "passive"))
      (node (ref "R2") (pin "2") (pinfunction "2_2") (pintype "passive"))
      (node (ref "U2") (pin "131") (pinfunction "AVDD_131") (pintype "power_in"))
    )
    (net (code "65") (name "Net-(U2B-TCK)") (class "Default")
      (node (ref "JP2") (pin "8") (pinfunction "8_8") (pintype "passive"))
      (node (ref "U2") (pin "139") (pinfunction "TCK_139") (pintype "input"))
    )
    (net (code "66") (name "Net-(U2B-TDI)") (class "Default")
      (node (ref "JP2") (pin "12") (pinfunction "12_12") (pintype "passive"))
      (node (ref "U2") (pin "137") (pinfunction "TDI_137") (pintype "input"))
    )
    (net (code "67") (name "Net-(U2B-TDO)") (class "Default")
      (node (ref "JP2") (pin "14") (pinfunction "14_14") (pintype "passive"))
      (node (ref "U2") (pin "136") (pinfunction "TDO_136") (pintype "output"))
    )
    (net (code "68") (name "Net-(U2B-TMS)") (class "Default")
      (node (ref "JP2") (pin "6") (pinfunction "6_6") (pintype "passive"))
      (node (ref "U2") (pin "140") (pinfunction "TMS_140") (pintype "input"))
    )
    (net (code "69") (name "Net-(U2B-~{EMU})") (class "Default")
      (node (ref "JP2") (pin "2") (pinfunction "2_2") (pintype "passive"))
      (node (ref "U2") (pin "135") (pinfunction "~{EMU}_135") (pintype "output"))
    )
    (net (code "70") (name "Net-(U2B-~{TRST})") (class "Default")
      (node (ref "JP2") (pin "10") (pinfunction "10_10") (pintype "passive"))
      (node (ref "U2") (pin "138") (pinfunction "~{TRST}_138") (pintype "input"))
    )
    (net (code "71") (name "VCC") (class "Default")
      (node (ref "C11") (pin "2") (pinfunction "2_2") (pintype "passive"))
      (node (ref "C13") (pin "2") (pinfunction "2_2") (pintype "passive"))
      (node (ref "C15") (pin "2") (pinfunction "2_2") (pintype "passive"))
      (node (ref "C17") (pin "2") (pinfunction "2_2") (pintype "passive"))
      (node (ref "C19") (pin "2") (pinfunction "2_2") (pintype "passive"))
      (node (ref "C23") (pin "2") (pinfunction "2_2") (pintype "passive"))
      (node (ref "C25") (pin "2") (pinfunction "2_2") (pintype "passive"))
      (node (ref "C39") (pin "2") (pinfunction "2_2") (pintype "passive"))
      (node (ref "C41") (pin "2") (pinfunction "2_2") (pintype "passive"))
      (node (ref "C43") (pin "2") (pinfunction "2_2") (pintype "passive"))
      (node (ref "C45") (pin "2") (pinfunction "2_2") (pintype "passive"))
      (node (ref "C47") (pin "2") (pinfunction "2_2") (pintype "passive"))
      (node (ref "C51") (pin "2") (pinfunction "2_2") (pintype "passive"))
      (node (ref "C53") (pin "2") (pinfunction "2_2") (pintype "passive"))
      (node (ref "U1") (pin "116") (pinfunction "VDDEXT_116") (pintype "power_in"))
      (node (ref "U1") (pin "130") (pinfunction "VDDEXT_130") (pintype "power_in"))
      (node (ref "U1") (pin "144") (pinfunction "VDDEXT_144") (pintype "power_in"))
      (node (ref "U1") (pin "21") (pinfunction "VDDEXT_21") (pintype "power_in"))
      (node (ref "U1") (pin "31") (pinfunction "VDDEXT_31") (pintype "power_in"))
      (node (ref "U1") (pin "45") (pinfunction "VDDEXT_45") (pintype "power_in"))
      (node (ref "U1") (pin "5") (pinfunction "BOOTCFG1_5") (pintype "input"))
      (node (ref "U1") (pin "59") (pinfunction "VDDEXT_59") (pintype "power_in"))
      (node (ref "U1") (pin "7") (pinfunction "VDDEXT_7") (pintype "power_in"))
      (node (ref "U1") (pin "73") (pinfunction "VDDEXT_73") (pintype "power_in"))
      (node (ref "U1") (pin "93") (pinfunction "VDDEXT_93") (pintype "power_in"))
      (node (ref "U2") (pin "116") (pinfunction "VDDEXT_116") (pintype "power_in"))
      (node (ref "U2") (pin "130") (pinfunction "VDDEXT_130") (pintype "power_in"))
      (node (ref "U2") (pin "144") (pinfunction "VDDEXT_144") (pintype "power_in"))
      (node (ref "U2") (pin "21") (pinfunction "VDDEXT_21") (pintype "power_in"))
      (node (ref "U2") (pin "31") (pinfunction "VDDEXT_31") (pintype "power_in"))
      (node (ref "U2") (pin "45") (pinfunction "VDDEXT_45") (pintype "power_in"))
      (node (ref "U2") (pin "5") (pinfunction "BOOTCFG1_5") (pintype "input"))
      (node (ref "U2") (pin "59") (pinfunction "VDDEXT_59") (pintype "power_in"))
      (node (ref "U2") (pin "7") (pinfunction "VDDEXT_7") (pintype "power_in"))
      (node (ref "U2") (pin "73") (pinfunction "VDDEXT_73") (pintype "power_in"))
      (node (ref "U2") (pin "93") (pinfunction "VDDEXT_93") (pintype "power_in"))
    )
    (net (code "72") (name "unconnected-(JP1-Pad3)") (class "Default")
      (node (ref "JP1") (pin "3") (pinfunction "3_3") (pintype "passive"))
    )
    (net (code "73") (name "unconnected-(JP2-Pad3)") (class "Default")
      (node (ref "JP2") (pin "3") (pinfunction "3_3") (pintype "passive"))
    )
    (net (code "74") (name "unconnected-(U1B-CLKOUT-Pad134)") (class "Default")
      (node (ref "U1") (pin "134") (pinfunction "CLKOUT_134") (pintype "output"))
    )
    (net (code "75") (name "unconnected-(U1B-DAI1-Pad53)") (class "Default")
      (node (ref "U1") (pin "53") (pinfunction "DAI1_53") (pintype "bidirectional"))
    )
    (net (code "76") (name "unconnected-(U1B-DAI2-Pad56)") (class "Default")
      (node (ref "U1") (pin "56") (pinfunction "DAI2_56") (pintype "bidirectional"))
    )
    (net (code "77") (name "unconnected-(U1B-DAI3-Pad57)") (class "Default")
      (node (ref "U1") (pin "57") (pinfunction "DAI3_57") (pintype "bidirectional"))
    )
    (net (code "78") (name "unconnected-(U1B-DAI4-Pad62)") (class "Default")
      (node (ref "U1") (pin "62") (pinfunction "DAI4_62") (pintype "bidirectional"))
    )
    (net (code "79") (name "unconnected-(U1B-DAI5-Pad63)") (class "Default")
      (node (ref "U1") (pin "63") (pinfunction "DAI5_63") (pintype "bidirectional"))
    )
    (net (code "80") (name "unconnected-(U1B-DAI6-Pad64)") (class "Default")
      (node (ref "U1") (pin "64") (pinfunction "DAI6_64") (pintype "bidirectional"))
    )
    (net (code "81") (name "unconnected-(U1B-DAI7-Pad65)") (class "Default")
      (node (ref "U1") (pin "65") (pinfunction "DAI7_65") (pintype "bidirectional"))
    )
    (net (code "82") (name "unconnected-(U1B-DAI8-Pad70)") (class "Default")
      (node (ref "U1") (pin "70") (pinfunction "DAI8_70") (pintype "bidirectional"))
    )
    (net (code "83") (name "unconnected-(U1B-DAI9-Pad71)") (class "Default")
      (node (ref "U1") (pin "71") (pinfunction "DAI9_71") (pintype "bidirectional"))
    )
    (net (code "84") (name "unconnected-(U1B-DAI10-Pad77)") (class "Default")
      (node (ref "U1") (pin "77") (pinfunction "DAI10_77") (pintype "bidirectional"))
    )
    (net (code "85") (name "unconnected-(U1B-DAI11-Pad78)") (class "Default")
      (node (ref "U1") (pin "78") (pinfunction "DAI11_78") (pintype "bidirectional"))
    )
    (net (code "86") (name "unconnected-(U1B-DAI12-Pad79)") (class "Default")
      (node (ref "U1") (pin "79") (pinfunction "DAI12_79") (pintype "bidirectional"))
    )
    (net (code "87") (name "unconnected-(U1B-DAI13-Pad80)") (class "Default")
      (node (ref "U1") (pin "80") (pinfunction "DAI13_80") (pintype "bidirectional"))
    )
    (net (code "88") (name "unconnected-(U1B-DAI14-Pad81)") (class "Default")
      (node (ref "U1") (pin "81") (pinfunction "DAI14_81") (pintype "bidirectional"))
    )
    (net (code "89") (name "unconnected-(U1B-DAI15-Pad82)") (class "Default")
      (node (ref "U1") (pin "82") (pinfunction "DAI15_82") (pintype "bidirectional"))
    )
    (net (code "90") (name "unconnected-(U1B-DAI16-Pad86)") (class "Default")
      (node (ref "U1") (pin "86") (pinfunction "DAI16_86") (pintype "bidirectional"))
    )
    (net (code "91") (name "unconnected-(U1B-DAI17-Pad87)") (class "Default")
      (node (ref "U1") (pin "87") (pinfunction "DAI17_87") (pintype "bidirectional"))
    )
    (net (code "92") (name "unconnected-(U1B-DAI18-Pad88)") (class "Default")
      (node (ref "U1") (pin "88") (pinfunction "DAI18_88") (pintype "bidirectional"))
    )
    (net (code "93") (name "unconnected-(U1B-DAI19-Pad89)") (class "Default")
      (node (ref "U1") (pin "89") (pinfunction "DAI19_89") (pintype "bidirectional"))
    )
    (net (code "94") (name "unconnected-(U1B-DAI20-Pad94)") (class "Default")
      (node (ref "U1") (pin "94") (pinfunction "DAI20_94") (pintype "bidirectional"))
    )
    (net (code "95") (name "unconnected-(U1B-MISO-Pad126)") (class "Default")
      (node (ref "U1") (pin "126") (pinfunction "MISO_126") (pintype "bidirectional"))
    )
    (net (code "96") (name "unconnected-(U1B-MOSI-Pad127)") (class "Default")
      (node (ref "U1") (pin "127") (pinfunction "MOSI_127") (pintype "bidirectional"))
    )
    (net (code "97") (name "unconnected-(U1B-SPICLK-Pad125)") (class "Default")
      (node (ref "U1") (pin "125") (pinfunction "SPICLK_125") (pintype "bidirectional"))
    )
    (net (code "98") (name "unconnected-(U1B-XTAL-Pad143)") (class "Default")
      (node (ref "U1") (pin "143") (pinfunction "XTAL_143") (pintype "output"))
    )
    (net (code "99") (name "unconnected-(U1B-~{SPIDS}-Pad122)") (class "Default")
      (node (ref "U1") (pin "122") (pinfunction "~{SPIDS}_122") (pintype "input"))
    )
    (net (code "100") (name "unconnected-(U2B-CLKOUT-Pad134)") (class "Default")
      (node (ref "U2") (pin "134") (pinfunction "CLKOUT_134") (pintype "output"))
    )
    (net (code "101") (name "unconnected-(U2B-DAI1-Pad53)") (class "Default")
      (node (ref "U2") (pin "53") (pinfunction "DAI1_53") (pintype "bidirectional"))
    )
    (net (code "102") (name "unconnected-(U2B-DAI2-Pad56)") (class "Default")
      (node (ref "U2") (pin "56") (pinfunction "DAI2_56") (pintype "bidirectional"))
    )
    (net (code "103") (name "unconnected-(U2B-DAI3-Pad57)") (class "Default")
      (node (ref "U2") (pin "57") (pinfunction "DAI3_57") (pintype "bidirectional"))
    )
    (net (code "104") (name "unconnected-(U2B-DAI4-Pad62)") (class "Default")
      (node (ref "U2") (pin "62") (pinfunction "DAI4_62") (pintype "bidirectional"))
    )
    (net (code "105") (name "unconnected-(U2B-DAI5-Pad63)") (class "Default")
      (node (ref "U2") (pin "63") (pinfunction "DAI5_63") (pintype "bidirectional"))
    )
    (net (code "106") (name "unconnected-(U2B-DAI6-Pad64)") (class "Default")
      (node (ref "U2") (pin "64") (pinfunction "DAI6_64") (pintype "bidirectional"))
    )
    (net (code "107") (name "unconnected-(U2B-DAI7-Pad65)") (class "Default")
      (node (ref "U2") (pin "65") (pinfunction "DAI7_65") (pintype "bidirectional"))
    )
    (net (code "108") (name "unconnected-(U2B-DAI8-Pad70)") (class "Default")
      (node (ref "U2") (pin "70") (pinfunction "DAI8_70") (pintype "bidirectional"))
    )
    (net (code "109") (name "unconnected-(U2B-DAI9-Pad71)") (class "Default")
      (node (ref "U2") (pin "71") (pinfunction "DAI9_71") (pintype "bidirectional"))
    )
    (net (code "110") (name "unconnected-(U2B-DAI10-Pad77)") (class "Default")
      (node (ref "U2") (pin "77") (pinfunction "DAI10_77") (pintype "bidirectional"))
    )
    (net (code "111") (name "unconnected-(U2B-DAI11-Pad78)") (class "Default")
      (node (ref "U2") (pin "78") (pinfunction "DAI11_78") (pintype "bidirectional"))
    )
    (net (code "112") (name "unconnected-(U2B-DAI12-Pad79)") (class "Default")
      (node (ref "U2") (pin "79") (pinfunction "DAI12_79") (pintype "bidirectional"))
    )
    (net (code "113") (name "unconnected-(U2B-DAI13-Pad80)") (class "Default")
      (node (ref "U2") (pin "80") (pinfunction "DAI13_80") (pintype "bidirectional"))
    )
    (net (code "114") (name "unconnected-(U2B-DAI14-Pad81)") (class "Default")
      (node (ref "U2") (pin "81") (pinfunction "DAI14_81") (pintype "bidirectional"))
    )
    (net (code "115") (name "unconnected-(U2B-DAI15-Pad82)") (class "Default")
      (node (ref "U2") (pin "82") (pinfunction "DAI15_82") (pintype "bidirectional"))
    )
    (net (code "116") (name "unconnected-(U2B-DAI16-Pad86)") (class "Default")
      (node (ref "U2") (pin "86") (pinfunction "DAI16_86") (pintype "bidirectional"))
    )
    (net (code "117") (name "unconnected-(U2B-DAI17-Pad87)") (class "Default")
      (node (ref "U2") (pin "87") (pinfunction "DAI17_87") (pintype "bidirectional"))
    )
    (net (code "118") (name "unconnected-(U2B-DAI18-Pad88)") (class "Default")
      (node (ref "U2") (pin "88") (pinfunction "DAI18_88") (pintype "bidirectional"))
    )
    (net (code "119") (name "unconnected-(U2B-DAI19-Pad89)") (class "Default")
      (node (ref "U2") (pin "89") (pinfunction "DAI19_89") (pintype "bidirectional"))
    )
    (net (code "120") (name "unconnected-(U2B-DAI20-Pad94)") (class "Default")
      (node (ref "U2") (pin "94") (pinfunction "DAI20_94") (pintype "bidirectional"))
    )
    (net (code "121") (name "unconnected-(U2B-MISO-Pad126)") (class "Default")
      (node (ref "U2") (pin "126") (pinfunction "MISO_126") (pintype "bidirectional"))
    )
    (net (code "122") (name "unconnected-(U2B-MOSI-Pad127)") (class "Default")
      (node (ref "U2") (pin "127") (pinfunction "MOSI_127") (pintype "bidirectional"))
    )
    (net (code "123") (name "unconnected-(U2B-SPICLK-Pad125)") (class "Default")
      (node (ref "U2") (pin "125") (pinfunction "SPICLK_125") (pintype "bidirectional"))
    )
    (net (code "124") (name "unconnected-(U2B-XTAL-Pad143)") (class "Default")
      (node (ref "U2") (pin "143") (pinfunction "XTAL_143") (pintype "output"))
    )
    (net (code "125") (name "unconnected-(U2B-~{SPIDS}-Pad122)") (class "Default")
      (node (ref "U2") (pin "122") (pinfunction "~{SPIDS}_122") (pintype "input"))
    )
  )
)
